# encoder_board.net
KiCad netlist of a schematic drawn in EAGLE
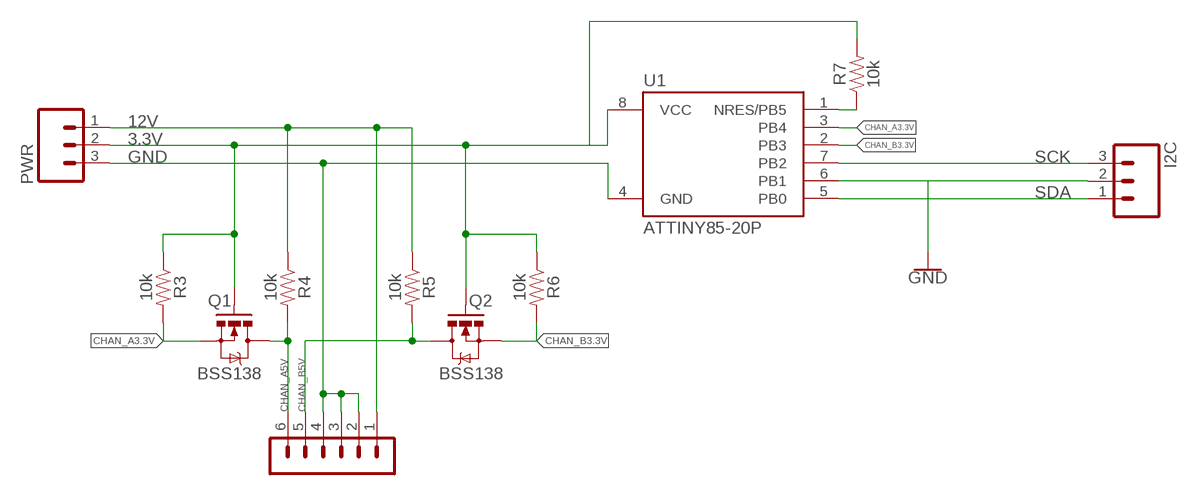
[diagram p0: schematic, sheet 1]

(export (version "E")
  (design (tool "Eeschema 10.0.6"))
  (components
    (comp (ref "ENCODER")
      (value "B6B-EH-A")
      (footprint "eagle-import:B6B-EH-A")
      (libsource (lib "eagle-import") (part "B6B-EH-A"))
    )
    (comp (ref "I2C")
      (value "CONN_03JST-PTH-VERT")
      (footprint "eagle-import:JST-3-PTH-VERT")
      (libsource (lib "eagle-import") (part "CONN_03JST-PTH-VERT"))
    )
    (comp (ref "PWR")
      (value "CONN_03JST-PTH-VERT")
      (footprint "eagle-import:JST-3-PTH-VERT")
      (libsource (lib "eagle-import") (part "CONN_03JST-PTH-VERT"))
    )
    (comp (ref "Q1")
      (value "BSS138")
      (footprint "eagle-import:SOT23-3")
      (libsource (lib "eagle-import") (part "MOSFET-NCHANNELSMD"))
    )
    (comp (ref "Q2")
      (value "BSS138")
      (footprint "eagle-import:SOT23-3")
      (libsource (lib "eagle-import") (part "MOSFET-NCHANNELSMD"))
    )
    (comp (ref "R3")
      (value "10k")
      (footprint "eagle-import:AXIAL-0.3")
      (libsource (lib "eagle-import") (part "10KOHM-HORIZ-1/4W-1%"))
    )
    (comp (ref "R4")
      (value "10k")
      (footprint "eagle-import:AXIAL-0.3")
      (libsource (lib "eagle-import") (part "10KOHM-HORIZ-1/4W-1%"))
    )
    (comp (ref "R5")
      (value "10k")
      (footprint "eagle-import:AXIAL-0.3")
      (libsource (lib "eagle-import") (part "10KOHM-HORIZ-1/4W-1%"))
    )
    (comp (ref "R6")
      (value "10k")
      (footprint "eagle-import:AXIAL-0.3")
      (libsource (lib "eagle-import") (part "10KOHM-HORIZ-1/4W-1%"))
    )
    (comp (ref "R7")
      (value "10k")
      (footprint "eagle-import:AXIAL-0.3")
      (libsource (lib "eagle-import") (part "10KOHM-HORIZ-1/4W-1%"))
    )
    (comp (ref "U1")
      (value "ATTINY85-20P")
      (footprint "eagle-import:PDIP08_300MIL")
      (libsource (lib "eagle-import") (part "ATTINY85P-20"))
    )
  )
  (nets
    (net (code "1") (name "/3.3V") (class "Default")
      (node (ref "PWR") (pin "2") (pinfunction "2_2") (pintype "passive"))
      (node (ref "Q1") (pin "1") (pinfunction "G_1") (pintype "passive"))
      (node (ref "Q2") (pin "1") (pinfunction "G_1") (pintype "passive"))
      (node (ref "R3") (pin "P$1") (pinfunction "1_P$1") (pintype "passive"))
      (node (ref "R6") (pin "P$1") (pinfunction "1_P$1") (pintype "passive"))
      (node (ref "R7") (pin "P$2") (pinfunction "2_P$2") (pintype "passive"))
      (node (ref "U1") (pin "8") (pinfunction "VCC_8") (pintype "power_in"))
    )
    (net (code "2") (name "/12V") (class "Default")
      (node (ref "ENCODER") (pin "1") (pinfunction "1_1") (pintype "passive"))
      (node (ref "PWR") (pin "1") (pinfunction "1_1") (pintype "passive"))
      (node (ref "R4") (pin "P$1") (pinfunction "1_P$1") (pintype "passive"))
      (node (ref "R5") (pin "P$1") (pinfunction "1_P$1") (pintype "passive"))
    )
    (net (code "3") (name "/CHAN_A5V") (class "Default")
      (node (ref "ENCODER") (pin "6") (pinfunction "6_6") (pintype "passive"))
      (node (ref "Q1") (pin "3") (pinfunction "D_3") (pintype "passive"))
      (node (ref "R4") (pin "P$2") (pinfunction "2_P$2") (pintype "passive"))
    )
    (net (code "4") (name "/CHAN_B5V") (class "Default")
      (node (ref "ENCODER") (pin "5") (pinfunction "5_5") (pintype "passive"))
      (node (ref "Q2") (pin "3") (pinfunction "D_3") (pintype "passive"))
      (node (ref "R5") (pin "P$2") (pinfunction "2_P$2") (pintype "passive"))
    )
    (net (code "5") (name "/SCK") (class "Default")
      (node (ref "I2C") (pin "3") (pinfunction "3_3") (pintype "passive"))
      (node (ref "U1") (pin "7") (pinfunction "PB2_7") (pintype "bidirectional"))
    )
    (net (code "6") (name "/SDA") (class "Default")
      (node (ref "I2C") (pin "1") (pinfunction "1_1") (pintype "passive"))
      (node (ref "U1") (pin "5") (pinfunction "PB0_5") (pintype "bidirectional"))
    )
    (net (code "7") (name "CHAN_A3.3V") (class "Default")
      (node (ref "Q1") (pin "2") (pinfunction "S_2") (pintype "passive"))
      (node (ref "R3") (pin "P$2") (pinfunction "2_P$2") (pintype "passive"))
      (node (ref "U1") (pin "3") (pinfunction "PB4_3") (pintype "bidirectional"))
    )
    (net (code "8") (name "CHAN_B3.3V") (class "Default")
      (node (ref "Q2") (pin "2") (pinfunction "S_2") (pintype "passive"))
      (node (ref "R6") (pin "P$2") (pinfunction "2_P$2") (pintype "passive"))
      (node (ref "U1") (pin "2") (pinfunction "PB3_2") (pintype "bidirectional"))
    )
    (net (code "9") (name "GND") (class "Default")
      (node (ref "ENCODER") (pin "2") (pinfunction "2_2") (pintype "passive"))
      (node (ref "ENCODER") (pin "3") (pinfunction "3_3") (pintype "passive"))
      (node (ref "ENCODER") (pin "4") (pinfunction "4_4") (pintype "passive"))
      (node (ref "I2C") (pin "2") (pinfunction "2_2") (pintype "passive"))
      (node (ref "PWR") (pin "3") (pinfunction "3_3") (pintype "passive"))
      (node (ref "U1") (pin "4") (pinfunction "GND_4") (pintype "power_in"))
      (node (ref "U1") (pin "6") (pinfunction "PB1_6") (pintype "bidirectional"))
    )
    (net (code "10") (name "Net-(R7-1)") (class "Default")
      (node (ref "R7") (pin "P$1") (pinfunction "1_P$1") (pintype "passive"))
      (node (ref "U1") (pin "1") (pinfunction "NRES/PB5_1") (pintype "bidirectional"))
    )
  )
)
